# USB_to_Serial.net
KiCad netlist of a schematic drawn in Altium Designer
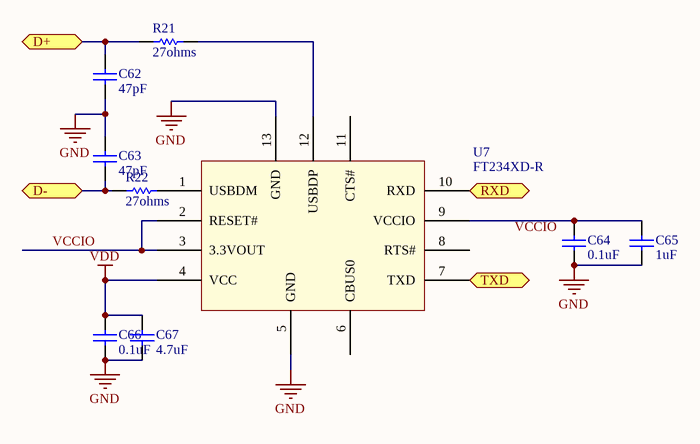
[diagram p0: USB_to_Serial.SchDoc]

(export (version "E")
  (design (tool "Eeschema 10.0.6"))
  (components
    (comp (ref "C62")
      (value "47pF")
      (footprint "0603_Cap")
      (description "CAP CER 47PF 150V C0G/NP0 0603")
      (fields
        (field (name "MANUFACTURER") "Knowles Syfer")
        (field (name "MANUFACTURER PART NUMBER") "060321500470FQTLSM")
      )
      (libsource (lib "Sitara") (part "060321500470FQTLSM"))
    )
    (comp (ref "C63")
      (value "47pF")
      (footprint "0603_Cap")
      (description "CAP CER 47PF 150V C0G/NP0 0603")
      (fields
        (field (name "MANUFACTURER") "Knowles Syfer")
        (field (name "MANUFACTURER PART NUMBER") "060321500470FQTLSM")
      )
      (libsource (lib "Sitara") (part "060321500470FQTLSM"))
    )
    (comp (ref "C64")
      (value "0.1uF")
      (footprint "0603_Cap")
      (description "CAP CER 0.1UF 16V X7R 0603")
      (fields
        (field (name "MANUFACTURER") "AVX Corporation")
        (field (name "MANUFACTURER PART NUMBER") "0603YC104KAT4A")
      )
      (libsource (lib "Sitara") (part "0603YC104KAT4A"))
    )
    (comp (ref "C65")
      (value "1uF")
      (footprint "0603_Cap")
      (description "CAP CER 1uF SMD")
      (fields
        (field (name "MANUFACTURER") "Taiyo Yuden")
        (field (name "MANUFACTURER PART NUMBER") "JMK107C6105KA-T")
      )
      (libsource (lib "Sitara") (part "JMK107C6105KA-T"))
    )
    (comp (ref "C66")
      (value "0.1uF")
      (footprint "0603_Cap")
      (description "CAP CER 0.1UF 16V X7R 0603")
      (fields
        (field (name "MANUFACTURER") "AVX Corporation")
        (field (name "MANUFACTURER PART NUMBER") "0603YC104KAT4A")
      )
      (libsource (lib "Sitara") (part "0603YC104KAT4A"))
    )
    (comp (ref "C67")
      (value "4.7uF")
      (footprint "0603_Cap")
      (fields
        (field (name "MANUFACTURER") "Taiyo Yuden")
        (field (name "MANUFACTURER PART NUMBER") "JMK107BJ475MAHT")
        (field (name "TOLERANCE") "±20%")
      )
      (libsource (lib "Sitara") (part "JMK107BJ475MAHT"))
    )
    (comp (ref "R21")
      (value "27ohms")
      (footprint "0603_RES")
      (description "RES SMD 27 OHM 0.1% 1/10W 0603")
      (fields
        (field (name "MANUFACTURER") "Yageo")
        (field (name "MANUFACTURER PART NUMBER") "RT0603BRB0727RL")
      )
      (libsource (lib "Sitara") (part "RT0603BRB0727RL"))
    )
    (comp (ref "R22")
      (value "27ohms")
      (footprint "0603_RES")
      (description "RES SMD 27 OHM 0.1% 1/10W 0603")
      (fields
        (field (name "MANUFACTURER") "Yageo")
        (field (name "MANUFACTURER PART NUMBER") "RT0603BRB0727RL")
      )
      (libsource (lib "Sitara") (part "RT0603BRB0727RL"))
    )
    (comp (ref "U7")
      (value "FT234XD-R")
      (footprint "DFN_12_FT234XD")
      (description "IC USB SERIAL BASIC UART 12DFN")
      (fields (field (name "MANUFACTURER") "FTDI, Future Technology Devices International Ltd"))
      (libsource (lib "Sitara") (part "FT234XD-R"))
    )
  )
  (nets
    (net (code "1") (name "/D+") (class "Default")
      (node (ref "C62") (pin "2") (pinfunction "2_2") (pintype "passive"))
      (node (ref "R21") (pin "1") (pinfunction "1_1") (pintype "passive"))
    )
    (net (code "2") (name "/D-") (class "Default")
      (node (ref "C63") (pin "1") (pinfunction "1_1") (pintype "passive"))
      (node (ref "R22") (pin "1") (pinfunction "1_1") (pintype "passive"))
    )
    (net (code "3") (name "/RXD") (class "Default")
      (node (ref "U7") (pin "10") (pinfunction "RXD_10") (pintype "passive"))
    )
    (net (code "4") (name "/TXD") (class "Default")
      (node (ref "U7") (pin "7") (pinfunction "TXD_7") (pintype "passive"))
    )
    (net (code "5") (name "/VCCIO") (class "Default")
      (node (ref "U7") (pin "2") (pinfunction "RESET#_2") (pintype "passive"))
      (node (ref "U7") (pin "3") (pinfunction "3.3VOUT_3") (pintype "passive"))
    )
    (net (code "6") (name "GND") (class "Default")
      (node (ref "C62") (pin "1") (pinfunction "1_1") (pintype "passive"))
      (node (ref "C63") (pin "2") (pinfunction "2_2") (pintype "passive"))
      (node (ref "C64") (pin "1") (pinfunction "1_1") (pintype "passive"))
      (node (ref "C65") (pin "1") (pinfunction "1_1") (pintype "passive"))
      (node (ref "C66") (pin "1") (pinfunction "1_1") (pintype "passive"))
      (node (ref "C67") (pin "1") (pinfunction "1_1") (pintype "passive"))
      (node (ref "U7") (pin "13") (pinfunction "GND_13") (pintype "passive"))
      (node (ref "U7") (pin "5") (pinfunction "GND_5") (pintype "passive"))
    )
    (net (code "7") (name "Net-(U7-USBDP)") (class "Default")
      (node (ref "R21") (pin "2") (pinfunction "2_2") (pintype "passive"))
      (node (ref "U7") (pin "12") (pinfunction "USBDP_12") (pintype "passive"))
    )
    (net (code "8") (name "Net-(U7-VCCIO)") (class "Default")
      (node (ref "C64") (pin "2") (pinfunction "2_2") (pintype "passive"))
      (node (ref "C65") (pin "2") (pinfunction "2_2") (pintype "passive"))
      (node (ref "U7") (pin "9") (pinfunction "VCCIO_9") (pintype "passive"))
    )
    (net (code "9") (name "VDD") (class "Default")
      (node (ref "C66") (pin "2") (pinfunction "2_2") (pintype "passive"))
      (node (ref "C67") (pin "2") (pinfunction "2_2") (pintype "passive"))
      (node (ref "U7") (pin "4") (pinfunction "VCC_4") (pintype "passive"))
    )
    (net (code "10") (name "unconnected-(R22-Pad2)") (class "Default")
      (node (ref "R22") (pin "2") (pinfunction "2_2") (pintype "passive"))
    )
    (net (code "11") (name "unconnected-(U7-CBUS0-Pad6)") (class "Default")
      (node (ref "U7") (pin "6") (pinfunction "CBUS0_6") (pintype "passive"))
    )
    (net (code "12") (name "unconnected-(U7-CTS#-Pad11)") (class "Default")
      (node (ref "U7") (pin "11") (pinfunction "CTS#_11") (pintype "passive"))
    )
    (net (code "13") (name "unconnected-(U7-RTS#-Pad8)") (class "Default")
      (node (ref "U7") (pin "8") (pinfunction "RTS#_8") (pintype "passive"))
    )
    (net (code "14") (name "unconnected-(U7-USBDM-Pad1)") (class "Default")
      (node (ref "U7") (pin "1") (pinfunction "USBDM_1") (pintype "passive"))
    )
  )
)
